# duet06_exp_2020-12-20_20-36-14.net
KiCad netlist of a schematic drawn in EasyEDA
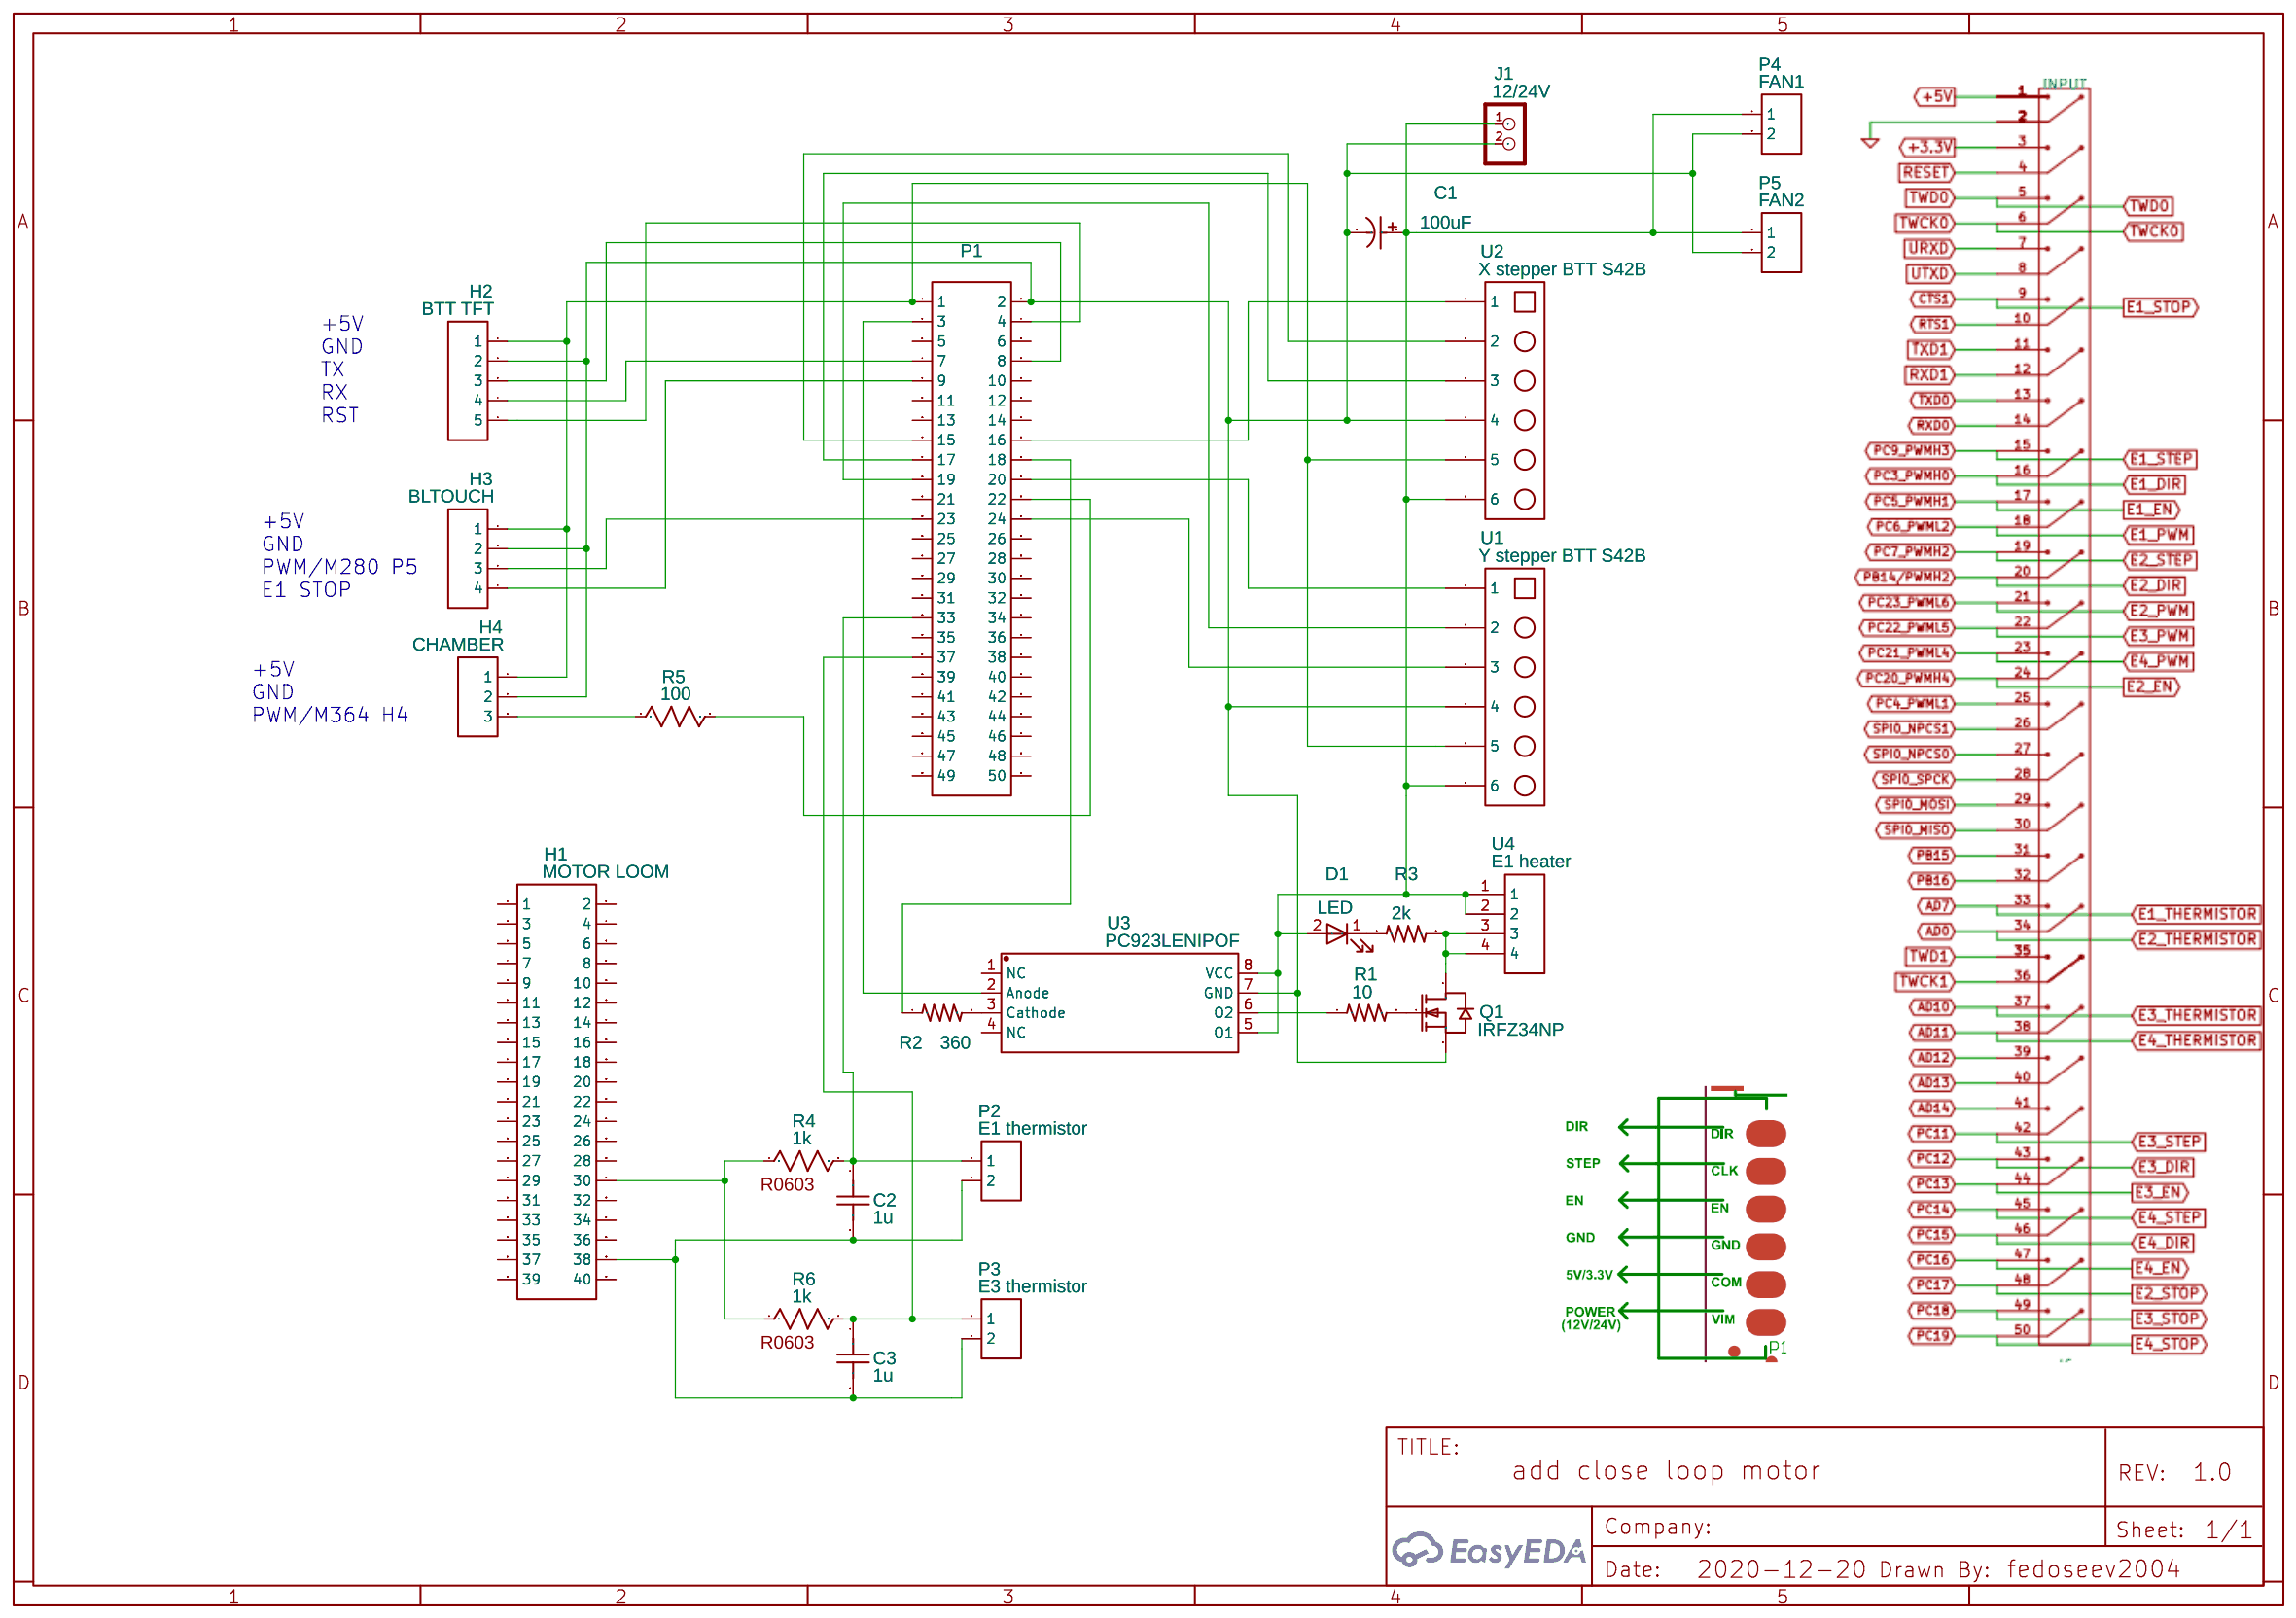
[diagram p0: schematic sheet]

(export (version "E")
  (design (tool "Eeschema 10.0.6"))
  (components
    (comp (ref "C1")
      (value "100uF")
      (fields
        (field (name "BOM_Manufacturer Part") "100uF 63V 8*14")
        (field (name "BOM_Supplier Part") "C45674")
      )
      (libsource (lib "") (part "100uF 63V 8*14"))
    )
    (comp (ref "C2") (value "1u") (libsource (lib "") (part "C_0603_US")))
    (comp (ref "C3") (value "1u") (libsource (lib "") (part "C_0603_US")))
    (comp (ref "D1") (value "LED") (libsource (lib "") (part "LED")))
    (comp (ref "H1")
      (value "MOTOR LOOM")
      (fields (field (name "BOM_Supplier Part") "C50982"))
      (libsource (lib "") (part "HDR-F-2.54_2x20"))
    )
    (comp (ref "H2")
      (value "BTT TFT")
      (fields (field (name "BOM_Supplier Part") "C50950"))
      (libsource (lib "") (part "HDR-F-2.54_1x5"))
    )
    (comp (ref "H3")
      (value "BLTOUCH")
      (fields (field (name "BOM_Supplier Part") "C225501"))
      (libsource (lib "") (part "HDR-F-2.54_1x4"))
    )
    (comp (ref "H4")
      (value "CHAMBER")
      (fields (field (name "BOM_Supplier Part") "C146690"))
      (libsource (lib "") (part "HDR-F-2.54_1x3"))
    )
    (comp (ref "J1") (value "12/24V") (libsource (lib "") (part "CON_TERMINAL_BLOCK_02-5MM")))
    (comp (ref "P1")
      (value "Header-Female-2.54_2x25")
      (fields
        (field (name "BOM_Manufacturer Part") "2.54mm 2*20PFemale header")
        (field (name "BOM_Supplier Part") "C50982")
      )
      (libsource (lib "") (part "Header-Female-2.54_2x25"))
    )
    (comp (ref "P2") (value "E1 thermistor") (libsource (lib "") (part "CONN-TH_2P-P5.00")))
    (comp (ref "P3") (value "E3 thermistor") (libsource (lib "") (part "CONN-TH_2P-P5.00")))
    (comp (ref "P4") (value "FAN1") (libsource (lib "") (part "CONN-TH_2P-P5.00")))
    (comp (ref "P5") (value "FAN2") (libsource (lib "") (part "CONN-TH_2P-P5.00")))
    (comp (ref "Q1")
      (value "IRFZ34NP")
      (fields (field (name "BOM_Supplier Part") "C878828"))
      (libsource (lib "") (part "IRFZ34NP"))
    )
    (comp (ref "R1") (value "10") (libsource (lib "") (part "RESISTOR0805")))
    (comp (ref "R2") (value "360") (libsource (lib "") (part "RESISTOR0805")))
    (comp (ref "R3") (value "2k") (libsource (lib "") (part "RESISTOR0805")))
    (comp (ref "R4") (value "1k") (libsource (lib "") (part "R_0603_US_1")))
    (comp (ref "R5") (value "100") (libsource (lib "") (part "R_0603_US")))
    (comp (ref "R6") (value "1k") (libsource (lib "") (part "R_0603_US_1")))
    (comp (ref "U1")
      (value "Y stepper BTT S42B")
      (fields (field (name "BOM_Manufacturer Part") "JST_XH CONNECTOR"))
      (libsource (lib "") (part "JST_XH CONNECTOR 6P"))
    )
    (comp (ref "U2")
      (value "X stepper BTT S42B")
      (fields (field (name "BOM_Manufacturer Part") "JST_XH CONNECTOR"))
      (libsource (lib "") (part "JST_XH CONNECTOR 6P"))
    )
    (comp (ref "U3")
      (value "PC923LENIPOF")
      (fields (field (name "BOM_Supplier Part") "C47423"))
      (libsource (lib "") (part "PC923LENIPOF"))
    )
    (comp (ref "U4")
      (value "E1 heater")
      (fields (field (name "BOM_Manufacturer Part") "Molex_4x1"))
      (libsource (lib "") (part "Molex 4 Pins_Stiftleiste_Straight"))
    )
  )
  (nets
    (net (code "1") (name "Net-(C2-Pad1)") (class "Default")
      (node (ref "C2") (pin "1") (pinfunction "1_1") (pintype "unspecified"))
      (node (ref "P1") (pin "33") (pinfunction "33_33") (pintype "input"))
      (node (ref "P2") (pin "1") (pinfunction "1_1") (pintype "unspecified"))
      (node (ref "R4") (pin "2") (pinfunction "2_2") (pintype "unspecified"))
    )
    (net (code "2") (name "Net-(C2-Pad2)") (class "Default")
      (node (ref "C2") (pin "2") (pinfunction "2_2") (pintype "unspecified"))
      (node (ref "C3") (pin "2") (pinfunction "2_2") (pintype "unspecified"))
      (node (ref "H1") (pin "38") (pinfunction "38_38") (pintype "input"))
      (node (ref "P2") (pin "2") (pinfunction "2_2") (pintype "unspecified"))
      (node (ref "P3") (pin "2") (pinfunction "2_2") (pintype "unspecified"))
    )
    (net (code "3") (name "Net-(C3-Pad1)") (class "Default")
      (node (ref "C3") (pin "1") (pinfunction "1_1") (pintype "unspecified"))
      (node (ref "P1") (pin "37") (pinfunction "37_37") (pintype "input"))
      (node (ref "P3") (pin "1") (pinfunction "1_1") (pintype "unspecified"))
      (node (ref "R6") (pin "2") (pinfunction "2_2") (pintype "unspecified"))
    )
    (net (code "4") (name "Net-(D1-A)") (class "Default")
      (node (ref "C1") (pin "1") (pinfunction "1_1") (pintype "input"))
      (node (ref "D1") (pin "2") (pinfunction "A_2") (pintype "unspecified"))
      (node (ref "J1") (pin "1") (pinfunction "1_1") (pintype "unspecified"))
      (node (ref "P4") (pin "1") (pinfunction "1_1") (pintype "unspecified"))
      (node (ref "P5") (pin "1") (pinfunction "1_1") (pintype "unspecified"))
      (node (ref "U1") (pin "6") (pinfunction "6_6") (pintype "unspecified"))
      (node (ref "U2") (pin "6") (pinfunction "6_6") (pintype "unspecified"))
      (node (ref "U3") (pin "5") (pinfunction "O1_5") (pintype "unspecified"))
      (node (ref "U3") (pin "8") (pinfunction "VCC_8") (pintype "unspecified"))
      (node (ref "U4") (pin "1") (pinfunction "1_1") (pintype "unspecified"))
      (node (ref "U4") (pin "2") (pinfunction "2_2") (pintype "unspecified"))
    )
    (net (code "5") (name "Net-(D1-K)") (class "Default")
      (node (ref "D1") (pin "1") (pinfunction "K_1") (pintype "unspecified"))
      (node (ref "R3") (pin "1") (pinfunction "1_1") (pintype "unspecified"))
    )
    (net (code "6") (name "Net-(H1-Pad30)") (class "Default")
      (node (ref "H1") (pin "30") (pinfunction "30_30") (pintype "input"))
      (node (ref "R4") (pin "1") (pinfunction "1_1") (pintype "unspecified"))
      (node (ref "R6") (pin "1") (pinfunction "1_1") (pintype "unspecified"))
    )
    (net (code "7") (name "Net-(H2-Pad1)") (class "Default")
      (node (ref "H2") (pin "1") (pinfunction "1_1") (pintype "unspecified"))
      (node (ref "H3") (pin "1") (pinfunction "1_1") (pintype "unspecified"))
      (node (ref "H4") (pin "1") (pinfunction "1_1") (pintype "input"))
      (node (ref "P1") (pin "1") (pinfunction "1_1") (pintype "input"))
      (node (ref "U1") (pin "5") (pinfunction "5_5") (pintype "unspecified"))
      (node (ref "U2") (pin "5") (pinfunction "5_5") (pintype "unspecified"))
    )
    (net (code "8") (name "Net-(H2-Pad3)") (class "Default")
      (node (ref "H2") (pin "3") (pinfunction "3_3") (pintype "unspecified"))
      (node (ref "P1") (pin "8") (pinfunction "8_8") (pintype "input"))
    )
    (net (code "9") (name "Net-(H2-Pad4)") (class "Default")
      (node (ref "H2") (pin "4") (pinfunction "4_4") (pintype "unspecified"))
      (node (ref "P1") (pin "7") (pinfunction "7_7") (pintype "input"))
    )
    (net (code "10") (name "Net-(H2-Pad5)") (class "Default")
      (node (ref "H2") (pin "5") (pinfunction "5_5") (pintype "unspecified"))
      (node (ref "P1") (pin "4") (pinfunction "4_4") (pintype "input"))
    )
    (net (code "11") (name "Net-(H3-Pad3)") (class "Default")
      (node (ref "H3") (pin "3") (pinfunction "3_3") (pintype "unspecified"))
      (node (ref "P1") (pin "23") (pinfunction "23_23") (pintype "input"))
    )
    (net (code "12") (name "Net-(H3-Pad4)") (class "Default")
      (node (ref "H3") (pin "4") (pinfunction "4_4") (pintype "unspecified"))
      (node (ref "P1") (pin "9") (pinfunction "9_9") (pintype "input"))
    )
    (net (code "13") (name "Net-(H4-Pad3)") (class "Default")
      (node (ref "H4") (pin "3") (pinfunction "3_3") (pintype "input"))
      (node (ref "R5") (pin "1") (pinfunction "1_1") (pintype "unspecified"))
    )
    (net (code "14") (name "Net-(P1-Pad15)") (class "Default")
      (node (ref "P1") (pin "15") (pinfunction "15_15") (pintype "input"))
      (node (ref "U2") (pin "2") (pinfunction "2_2") (pintype "unspecified"))
    )
    (net (code "15") (name "Net-(P1-Pad16)") (class "Default")
      (node (ref "P1") (pin "16") (pinfunction "16_16") (pintype "input"))
      (node (ref "U2") (pin "1") (pinfunction "1_1") (pintype "unspecified"))
    )
    (net (code "16") (name "Net-(P1-Pad17)") (class "Default")
      (node (ref "P1") (pin "17") (pinfunction "17_17") (pintype "input"))
      (node (ref "U2") (pin "3") (pinfunction "3_3") (pintype "unspecified"))
    )
    (net (code "17") (name "Net-(P1-Pad18)") (class "Default")
      (node (ref "P1") (pin "18") (pinfunction "18_18") (pintype "input"))
      (node (ref "R2") (pin "1") (pinfunction "1_1") (pintype "unspecified"))
    )
    (net (code "18") (name "Net-(P1-Pad19)") (class "Default")
      (node (ref "P1") (pin "19") (pinfunction "19_19") (pintype "input"))
      (node (ref "U1") (pin "2") (pinfunction "2_2") (pintype "unspecified"))
    )
    (net (code "19") (name "Net-(P1-Pad20)") (class "Default")
      (node (ref "P1") (pin "20") (pinfunction "20_20") (pintype "input"))
      (node (ref "U1") (pin "1") (pinfunction "1_1") (pintype "unspecified"))
    )
    (net (code "20") (name "Net-(P1-Pad22)") (class "Default")
      (node (ref "P1") (pin "22") (pinfunction "22_22") (pintype "input"))
      (node (ref "R5") (pin "2") (pinfunction "2_2") (pintype "unspecified"))
    )
    (net (code "21") (name "Net-(P1-Pad24)") (class "Default")
      (node (ref "P1") (pin "24") (pinfunction "24_24") (pintype "input"))
      (node (ref "U1") (pin "3") (pinfunction "3_3") (pintype "unspecified"))
    )
    (net (code "22") (name "Net-(Q1-D)") (class "Default")
      (node (ref "Q1") (pin "2") (pinfunction "D_2") (pintype "unspecified"))
      (node (ref "R3") (pin "2") (pinfunction "2_2") (pintype "unspecified"))
      (node (ref "U4") (pin "3") (pinfunction "3_3") (pintype "unspecified"))
      (node (ref "U4") (pin "4") (pinfunction "4_4") (pintype "unspecified"))
    )
    (net (code "23") (name "Net-(Q1-G)") (class "Default")
      (node (ref "Q1") (pin "1") (pinfunction "G_1") (pintype "unspecified"))
      (node (ref "R1") (pin "2") (pinfunction "2_2") (pintype "unspecified"))
    )
    (net (code "24") (name "Net-(Q1-S)") (class "Default")
      (node (ref "C1") (pin "2") (pinfunction "2_2") (pintype "input"))
      (node (ref "H2") (pin "2") (pinfunction "2_2") (pintype "unspecified"))
      (node (ref "H3") (pin "2") (pinfunction "2_2") (pintype "unspecified"))
      (node (ref "H4") (pin "2") (pinfunction "2_2") (pintype "input"))
      (node (ref "J1") (pin "2") (pinfunction "2_2") (pintype "unspecified"))
      (node (ref "P1") (pin "2") (pinfunction "2_2") (pintype "input"))
      (node (ref "P4") (pin "2") (pinfunction "2_2") (pintype "unspecified"))
      (node (ref "P5") (pin "2") (pinfunction "2_2") (pintype "unspecified"))
      (node (ref "Q1") (pin "3") (pinfunction "S_3") (pintype "unspecified"))
      (node (ref "U1") (pin "4") (pinfunction "4_4") (pintype "unspecified"))
      (node (ref "U2") (pin "4") (pinfunction "4_4") (pintype "unspecified"))
      (node (ref "U3") (pin "7") (pinfunction "GND_7") (pintype "unspecified"))
    )
    (net (code "25") (name "Net-(U3-Anode)") (class "Default")
      (node (ref "P1") (pin "3") (pinfunction "3_3") (pintype "input"))
      (node (ref "U3") (pin "2") (pinfunction "Anode_2") (pintype "unspecified"))
    )
    (net (code "26") (name "Net-(U3-Cathode)") (class "Default")
      (node (ref "R2") (pin "2") (pinfunction "2_2") (pintype "unspecified"))
      (node (ref "U3") (pin "3") (pinfunction "Cathode_3") (pintype "unspecified"))
    )
    (net (code "27") (name "Net-(U3-O2)") (class "Default")
      (node (ref "R1") (pin "1") (pinfunction "1_1") (pintype "unspecified"))
      (node (ref "U3") (pin "6") (pinfunction "O2_6") (pintype "unspecified"))
    )
    (net (code "28") (name "unconnected-(H1-Pad1)") (class "Default")
      (node (ref "H1") (pin "1") (pinfunction "1_1") (pintype "input"))
    )
    (net (code "29") (name "unconnected-(H1-Pad2)") (class "Default")
      (node (ref "H1") (pin "2") (pinfunction "2_2") (pintype "input"))
    )
    (net (code "30") (name "unconnected-(H1-Pad3)") (class "Default")
      (node (ref "H1") (pin "3") (pinfunction "3_3") (pintype "input"))
    )
    (net (code "31") (name "unconnected-(H1-Pad4)") (class "Default")
      (node (ref "H1") (pin "4") (pinfunction "4_4") (pintype "input"))
    )
    (net (code "32") (name "unconnected-(H1-Pad5)") (class "Default")
      (node (ref "H1") (pin "5") (pinfunction "5_5") (pintype "input"))
    )
    (net (code "33") (name "unconnected-(H1-Pad6)") (class "Default")
      (node (ref "H1") (pin "6") (pinfunction "6_6") (pintype "input"))
    )
    (net (code "34") (name "unconnected-(H1-Pad7)") (class "Default")
      (node (ref "H1") (pin "7") (pinfunction "7_7") (pintype "input"))
    )
    (net (code "35") (name "unconnected-(H1-Pad8)") (class "Default")
      (node (ref "H1") (pin "8") (pinfunction "8_8") (pintype "input"))
    )
    (net (code "36") (name "unconnected-(H1-Pad9)") (class "Default")
      (node (ref "H1") (pin "9") (pinfunction "9_9") (pintype "input"))
    )
    (net (code "37") (name "unconnected-(H1-Pad10)") (class "Default")
      (node (ref "H1") (pin "10") (pinfunction "10_10") (pintype "input"))
    )
    (net (code "38") (name "unconnected-(H1-Pad11)") (class "Default")
      (node (ref "H1") (pin "11") (pinfunction "11_11") (pintype "input"))
    )
    (net (code "39") (name "unconnected-(H1-Pad12)") (class "Default")
      (node (ref "H1") (pin "12") (pinfunction "12_12") (pintype "input"))
    )
    (net (code "40") (name "unconnected-(H1-Pad13)") (class "Default")
      (node (ref "H1") (pin "13") (pinfunction "13_13") (pintype "input"))
    )
    (net (code "41") (name "unconnected-(H1-Pad14)") (class "Default")
      (node (ref "H1") (pin "14") (pinfunction "14_14") (pintype "input"))
    )
    (net (code "42") (name "unconnected-(H1-Pad15)") (class "Default")
      (node (ref "H1") (pin "15") (pinfunction "15_15") (pintype "input"))
    )
    (net (code "43") (name "unconnected-(H1-Pad16)") (class "Default")
      (node (ref "H1") (pin "16") (pinfunction "16_16") (pintype "input"))
    )
    (net (code "44") (name "unconnected-(H1-Pad17)") (class "Default")
      (node (ref "H1") (pin "17") (pinfunction "17_17") (pintype "input"))
    )
    (net (code "45") (name "unconnected-(H1-Pad18)") (class "Default")
      (node (ref "H1") (pin "18") (pinfunction "18_18") (pintype "input"))
    )
    (net (code "46") (name "unconnected-(H1-Pad19)") (class "Default")
      (node (ref "H1") (pin "19") (pinfunction "19_19") (pintype "input"))
    )
    (net (code "47") (name "unconnected-(H1-Pad20)") (class "Default")
      (node (ref "H1") (pin "20") (pinfunction "20_20") (pintype "input"))
    )
    (net (code "48") (name "unconnected-(H1-Pad21)") (class "Default")
      (node (ref "H1") (pin "21") (pinfunction "21_21") (pintype "input"))
    )
    (net (code "49") (name "unconnected-(H1-Pad22)") (class "Default")
      (node (ref "H1") (pin "22") (pinfunction "22_22") (pintype "input"))
    )
    (net (code "50") (name "unconnected-(H1-Pad23)") (class "Default")
      (node (ref "H1") (pin "23") (pinfunction "23_23") (pintype "input"))
    )
    (net (code "51") (name "unconnected-(H1-Pad24)") (class "Default")
      (node (ref "H1") (pin "24") (pinfunction "24_24") (pintype "input"))
    )
    (net (code "52") (name "unconnected-(H1-Pad25)") (class "Default")
      (node (ref "H1") (pin "25") (pinfunction "25_25") (pintype "input"))
    )
    (net (code "53") (name "unconnected-(H1-Pad26)") (class "Default")
      (node (ref "H1") (pin "26") (pinfunction "26_26") (pintype "input"))
    )
    (net (code "54") (name "unconnected-(H1-Pad27)") (class "Default")
      (node (ref "H1") (pin "27") (pinfunction "27_27") (pintype "input"))
    )
    (net (code "55") (name "unconnected-(H1-Pad28)") (class "Default")
      (node (ref "H1") (pin "28") (pinfunction "28_28") (pintype "input"))
    )
    (net (code "56") (name "unconnected-(H1-Pad29)") (class "Default")
      (node (ref "H1") (pin "29") (pinfunction "29_29") (pintype "input"))
    )
    (net (code "57") (name "unconnected-(H1-Pad31)") (class "Default")
      (node (ref "H1") (pin "31") (pinfunction "31_31") (pintype "input"))
    )
    (net (code "58") (name "unconnected-(H1-Pad32)") (class "Default")
      (node (ref "H1") (pin "32") (pinfunction "32_32") (pintype "input"))
    )
    (net (code "59") (name "unconnected-(H1-Pad33)") (class "Default")
      (node (ref "H1") (pin "33") (pinfunction "33_33") (pintype "input"))
    )
    (net (code "60") (name "unconnected-(H1-Pad34)") (class "Default")
      (node (ref "H1") (pin "34") (pinfunction "34_34") (pintype "input"))
    )
    (net (code "61") (name "unconnected-(H1-Pad35)") (class "Default")
      (node (ref "H1") (pin "35") (pinfunction "35_35") (pintype "input"))
    )
    (net (code "62") (name "unconnected-(H1-Pad36)") (class "Default")
      (node (ref "H1") (pin "36") (pinfunction "36_36") (pintype "input"))
    )
    (net (code "63") (name "unconnected-(H1-Pad37)") (class "Default")
      (node (ref "H1") (pin "37") (pinfunction "37_37") (pintype "input"))
    )
    (net (code "64") (name "unconnected-(H1-Pad39)") (class "Default")
      (node (ref "H1") (pin "39") (pinfunction "39_39") (pintype "input"))
    )
    (net (code "65") (name "unconnected-(H1-Pad40)") (class "Default")
      (node (ref "H1") (pin "40") (pinfunction "40_40") (pintype "input"))
    )
    (net (code "66") (name "unconnected-(P1-41-Pad31)") (class "Default")
      (node (ref "P1") (pin "31") (pinfunction "41_31") (pintype "input"))
    )
    (net (code "67") (name "unconnected-(P1-42-Pad32)") (class "Default")
      (node (ref "P1") (pin "32") (pinfunction "42_32") (pintype "input"))
    )
    (net (code "68") (name "unconnected-(P1-43-Pad33)") (class "Default")
      (node (ref "P1") (pin "33") (pinfunction "43_33") (pintype "input"))
    )
    (net (code "69") (name "unconnected-(P1-44-Pad34)") (class "Default")
      (node (ref "P1") (pin "34") (pinfunction "44_34") (pintype "input"))
    )
    (net (code "70") (name "unconnected-(P1-45-Pad35)") (class "Default")
      (node (ref "P1") (pin "35") (pinfunction "45_35") (pintype "input"))
    )
    (net (code "71") (name "unconnected-(P1-46-Pad36)") (class "Default")
      (node (ref "P1") (pin "36") (pinfunction "46_36") (pintype "input"))
    )
    (net (code "72") (name "unconnected-(P1-47-Pad37)") (class "Default")
      (node (ref "P1") (pin "37") (pinfunction "47_37") (pintype "input"))
    )
    (net (code "73") (name "unconnected-(P1-48-Pad38)") (class "Default")
      (node (ref "P1") (pin "38") (pinfunction "48_38") (pintype "input"))
    )
    (net (code "74") (name "unconnected-(P1-49-Pad39)") (class "Default")
      (node (ref "P1") (pin "39") (pinfunction "49_39") (pintype "input"))
    )
    (net (code "75") (name "unconnected-(P1-50-Pad40)") (class "Default")
      (node (ref "P1") (pin "40") (pinfunction "50_40") (pintype "input"))
    )
    (net (code "76") (name "unconnected-(P1-Pad5)") (class "Default")
      (node (ref "P1") (pin "5") (pinfunction "5_5") (pintype "input"))
    )
    (net (code "77") (name "unconnected-(P1-Pad6)") (class "Default")
      (node (ref "P1") (pin "6") (pinfunction "6_6") (pintype "input"))
    )
    (net (code "78") (name "unconnected-(P1-Pad10)") (class "Default")
      (node (ref "P1") (pin "10") (pinfunction "10_10") (pintype "input"))
    )
    (net (code "79") (name "unconnected-(P1-Pad11)") (class "Default")
      (node (ref "P1") (pin "11") (pinfunction "11_11") (pintype "input"))
    )
    (net (code "80") (name "unconnected-(P1-Pad12)") (class "Default")
      (node (ref "P1") (pin "12") (pinfunction "12_12") (pintype "input"))
    )
    (net (code "81") (name "unconnected-(P1-Pad13)") (class "Default")
      (node (ref "P1") (pin "13") (pinfunction "13_13") (pintype "input"))
    )
    (net (code "82") (name "unconnected-(P1-Pad14)") (class "Default")
      (node (ref "P1") (pin "14") (pinfunction "14_14") (pintype "input"))
    )
    (net (code "83") (name "unconnected-(P1-Pad21)") (class "Default")
      (node (ref "P1") (pin "21") (pinfunction "21_21") (pintype "input"))
    )
    (net (code "84") (name "unconnected-(P1-Pad25)") (class "Default")
      (node (ref "P1") (pin "25") (pinfunction "25_25") (pintype "input"))
    )
    (net (code "85") (name "unconnected-(P1-Pad26)") (class "Default")
      (node (ref "P1") (pin "26") (pinfunction "26_26") (pintype "input"))
    )
    (net (code "86") (name "unconnected-(P1-Pad27)") (class "Default")
      (node (ref "P1") (pin "27") (pinfunction "27_27") (pintype "input"))
    )
    (net (code "87") (name "unconnected-(P1-Pad28)") (class "Default")
      (node (ref "P1") (pin "28") (pinfunction "28_28") (pintype "input"))
    )
    (net (code "88") (name "unconnected-(P1-Pad29)") (class "Default")
      (node (ref "P1") (pin "29") (pinfunction "29_29") (pintype "input"))
    )
    (net (code "89") (name "unconnected-(P1-Pad30)") (class "Default")
      (node (ref "P1") (pin "30") (pinfunction "30_30") (pintype "input"))
    )
    (net (code "90") (name "unconnected-(P1-Pad31)") (class "Default")
      (node (ref "P1") (pin "31") (pinfunction "31_31") (pintype "input"))
    )
    (net (code "91") (name "unconnected-(P1-Pad32)") (class "Default")
      (node (ref "P1") (pin "32") (pinfunction "32_32") (pintype "input"))
    )
    (net (code "92") (name "unconnected-(P1-Pad34)") (class "Default")
      (node (ref "P1") (pin "34") (pinfunction "34_34") (pintype "input"))
    )
    (net (code "93") (name "unconnected-(P1-Pad35)") (class "Default")
      (node (ref "P1") (pin "35") (pinfunction "35_35") (pintype "input"))
    )
    (net (code "94") (name "unconnected-(P1-Pad36)") (class "Default")
      (node (ref "P1") (pin "36") (pinfunction "36_36") (pintype "input"))
    )
    (net (code "95") (name "unconnected-(P1-Pad38)") (class "Default")
      (node (ref "P1") (pin "38") (pinfunction "38_38") (pintype "input"))
    )
    (net (code "96") (name "unconnected-(P1-Pad39)") (class "Default")
      (node (ref "P1") (pin "39") (pinfunction "39_39") (pintype "input"))
    )
    (net (code "97") (name "unconnected-(P1-Pad40)") (class "Default")
      (node (ref "P1") (pin "40") (pinfunction "40_40") (pintype "input"))
    )
    (net (code "98") (name "unconnected-(U3-NC-Pad1)") (class "Default")
      (node (ref "U3") (pin "1") (pinfunction "NC_1") (pintype "unspecified"))
    )
    (net (code "99") (name "unconnected-(U3-NC-Pad4)") (class "Default")
      (node (ref "U3") (pin "4") (pinfunction "NC_4") (pintype "unspecified"))
    )
  )
)
